# sensor.net
KiCad netlist of a schematic drawn in EAGLE
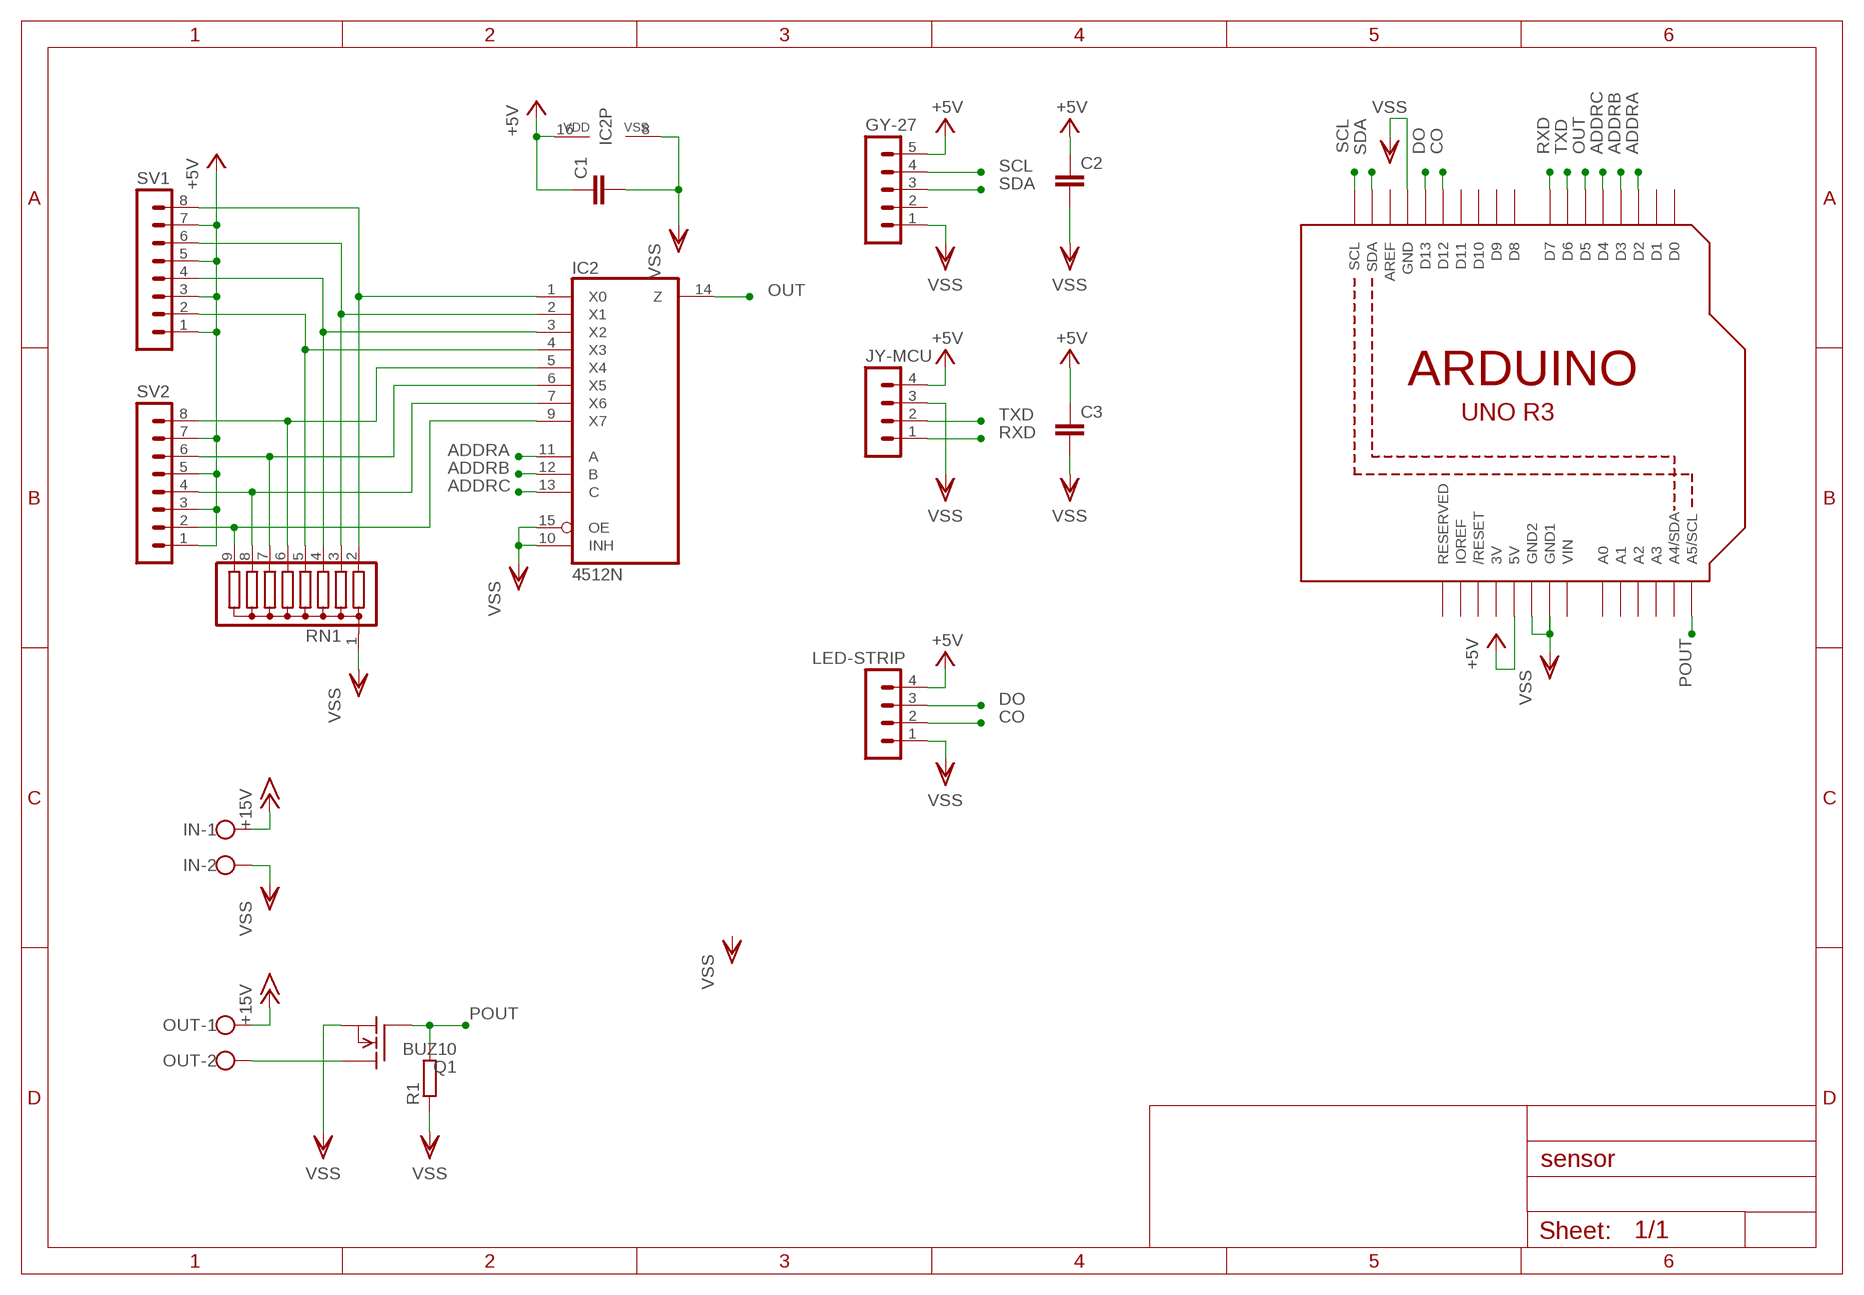
[diagram p0: schematic, sheet 1]

(export (version "E")
  (design (tool "Eeschema 10.0.6"))
  (components
    (comp (ref "C1")
      (value "C-EUC0805")
      (footprint "eagle-import:C0805")
      (libsource (lib "eagle-import") (part "C-EUC0805"))
    )
    (comp (ref "C2")
      (value "C-EUC0805")
      (footprint "eagle-import:C0805")
      (libsource (lib "eagle-import") (part "C-EUC0805"))
    )
    (comp (ref "C3")
      (value "C-EUC0805")
      (footprint "eagle-import:C0805")
      (libsource (lib "eagle-import") (part "C-EUC0805"))
    )
    (comp (ref "GY-27")
      (value "MA05-1")
      (footprint "eagle-import:MA05-1")
      (libsource (lib "eagle-import") (part "MA05-1"))
    )
    (comp (ref "IC2")
      (value "4512N")
      (footprint "eagle-import:DIL16")
      (libsource (lib "eagle-import") (part "4512N"))
    )
    (comp (ref "IN")
      (value "W237-102")
      (footprint "eagle-import:W237-102")
      (fields (field (name "MPN") "237-102"))
      (libsource (lib "eagle-import") (part "W237-102"))
    )
    (comp (ref "JY-MCU")
      (value "MA04-1")
      (footprint "eagle-import:MA04-1")
      (libsource (lib "eagle-import") (part "MA04-1"))
    )
    (comp (ref "LED-STRIP")
      (value "MA04-1")
      (footprint "eagle-import:MA04-1")
      (libsource (lib "eagle-import") (part "MA04-1"))
    )
    (comp (ref "OUT")
      (value "W237-102")
      (footprint "eagle-import:W237-102")
      (fields (field (name "MPN") "237-102"))
      (libsource (lib "eagle-import") (part "W237-102"))
    )
    (comp (ref "Q1")
      (value "BUZ10")
      (footprint "eagle-import:TO220")
      (libsource (lib "eagle-import") (part "BUZ10"))
    )
    (comp (ref "R1")
      (value "R-EU_M0805")
      (footprint "eagle-import:M0805")
      (libsource (lib "eagle-import") (part "R-EU_M0805"))
    )
    (comp (ref "RN1")
      (value "G08R")
      (footprint "eagle-import:SIL9")
      (libsource (lib "eagle-import") (part "G08R"))
    )
    (comp (ref "SV1")
      (value "MA08-1W")
      (footprint "eagle-import:MA08-1W")
      (libsource (lib "eagle-import") (part "MA08-1W"))
    )
    (comp (ref "SV2")
      (value "MA08-1W")
      (footprint "eagle-import:MA08-1W")
      (libsource (lib "eagle-import") (part "MA08-1W"))
    )
    (comp (ref "U1")
      (value "ARDUINOR3-DIMENSION")
      (footprint "eagle-import:ARDUINOR3")
      (libsource (lib "eagle-import") (part "ARDUINOR3-DIMENSION"))
    )
  )
  (nets
    (net (code "1") (name "+5V") (class "Default")
      (node (ref "C1") (pin "1") (pinfunction "1_1") (pintype "passive"))
      (node (ref "C2") (pin "1") (pinfunction "1_1") (pintype "passive"))
      (node (ref "C3") (pin "1") (pinfunction "1_1") (pintype "passive"))
      (node (ref "GY-27") (pin "5") (pinfunction "5_5") (pintype "passive"))
      (node (ref "IC2") (pin "16") (pinfunction "VDD_16") (pintype "power_in"))
      (node (ref "JY-MCU") (pin "4") (pinfunction "4_4") (pintype "passive"))
      (node (ref "LED-STRIP") (pin "4") (pinfunction "4_4") (pintype "passive"))
      (node (ref "SV1") (pin "1") (pinfunction "1_1") (pintype "passive"))
      (node (ref "SV1") (pin "3") (pinfunction "3_3") (pintype "passive"))
      (node (ref "SV1") (pin "5") (pinfunction "5_5") (pintype "passive"))
      (node (ref "SV1") (pin "7") (pinfunction "7_7") (pintype "passive"))
      (node (ref "SV2") (pin "1") (pinfunction "1_1") (pintype "passive"))
      (node (ref "SV2") (pin "3") (pinfunction "3_3") (pintype "passive"))
      (node (ref "SV2") (pin "5") (pinfunction "5_5") (pintype "passive"))
      (node (ref "SV2") (pin "7") (pinfunction "7_7") (pintype "passive"))
      (node (ref "U1") (pin "5V") (pinfunction "5V_5V") (pintype "power_in"))
    )
    (net (code "2") (name "+15V") (class "Default")
      (node (ref "IN") (pin "1") (pinfunction "KL_1") (pintype "passive"))
      (node (ref "OUT") (pin "1") (pinfunction "KL_1") (pintype "passive"))
    )
    (net (code "3") (name "/3V") (class "Default")
      (node (ref "U1") (pin "3V") (pinfunction "3V_3V") (pintype "power_in"))
    )
    (net (code "4") (name "/ADDRA") (class "Default")
      (node (ref "IC2") (pin "11") (pinfunction "A_11") (pintype "input"))
      (node (ref "U1") (pin "D2") (pinfunction "D2_D2") (pintype "bidirectional"))
    )
    (net (code "5") (name "/ADDRB") (class "Default")
      (node (ref "IC2") (pin "12") (pinfunction "B_12") (pintype "input"))
      (node (ref "U1") (pin "D3") (pinfunction "D3_D3") (pintype "bidirectional"))
    )
    (net (code "6") (name "/ADDRC") (class "Default")
      (node (ref "IC2") (pin "13") (pinfunction "C_13") (pintype "input"))
      (node (ref "U1") (pin "D4") (pinfunction "D4_D4") (pintype "bidirectional"))
    )
    (net (code "7") (name "/CO") (class "Default")
      (node (ref "LED-STRIP") (pin "2") (pinfunction "2_2") (pintype "passive"))
      (node (ref "U1") (pin "D12") (pinfunction "D12_D12") (pintype "bidirectional"))
    )
    (net (code "8") (name "/DO") (class "Default")
      (node (ref "LED-STRIP") (pin "3") (pinfunction "3_3") (pintype "passive"))
      (node (ref "U1") (pin "D13") (pinfunction "D13_D13") (pintype "bidirectional"))
    )
    (net (code "9") (name "/OUT") (class "Default")
      (node (ref "IC2") (pin "14") (pinfunction "Z_14") (pintype "tri_state"))
      (node (ref "U1") (pin "D5") (pinfunction "D5_D5") (pintype "bidirectional"))
    )
    (net (code "10") (name "/POUT") (class "Default")
      (node (ref "Q1") (pin "1") (pinfunction "G_1") (pintype "passive"))
      (node (ref "R1") (pin "2") (pinfunction "2_2") (pintype "passive"))
      (node (ref "U1") (pin "A5") (pinfunction "A5/SCL_A5") (pintype "bidirectional"))
    )
    (net (code "11") (name "/RXD") (class "Default")
      (node (ref "JY-MCU") (pin "1") (pinfunction "1_1") (pintype "passive"))
      (node (ref "U1") (pin "D7") (pinfunction "D7_D7") (pintype "bidirectional"))
    )
    (net (code "12") (name "/SCL") (class "Default")
      (node (ref "GY-27") (pin "4") (pinfunction "4_4") (pintype "passive"))
      (node (ref "U1") (pin "SCL") (pinfunction "SCL_SCL") (pintype "bidirectional"))
    )
    (net (code "13") (name "/SDA") (class "Default")
      (node (ref "GY-27") (pin "3") (pinfunction "3_3") (pintype "passive"))
      (node (ref "U1") (pin "SDA") (pinfunction "SDA_SDA") (pintype "bidirectional"))
    )
    (net (code "14") (name "/TXD") (class "Default")
      (node (ref "JY-MCU") (pin "2") (pinfunction "2_2") (pintype "passive"))
      (node (ref "U1") (pin "D6") (pinfunction "D6_D6") (pintype "bidirectional"))
    )
    (net (code "15") (name "/VIN") (class "Default")
      (node (ref "U1") (pin "VIN") (pinfunction "VIN_VIN") (pintype "power_in"))
    )
    (net (code "16") (name "Net-(IC2A-X0)") (class "Default")
      (node (ref "IC2") (pin "1") (pinfunction "X0_1") (pintype "input"))
      (node (ref "RN1") (pin "2") (pinfunction "2_2") (pintype "passive"))
      (node (ref "SV1") (pin "8") (pinfunction "8_8") (pintype "passive"))
    )
    (net (code "17") (name "Net-(IC2A-X1)") (class "Default")
      (node (ref "IC2") (pin "2") (pinfunction "X1_2") (pintype "input"))
      (node (ref "RN1") (pin "3") (pinfunction "3_3") (pintype "passive"))
      (node (ref "SV1") (pin "6") (pinfunction "6_6") (pintype "passive"))
    )
    (net (code "18") (name "Net-(IC2A-X2)") (class "Default")
      (node (ref "IC2") (pin "3") (pinfunction "X2_3") (pintype "input"))
      (node (ref "RN1") (pin "4") (pinfunction "4_4") (pintype "passive"))
      (node (ref "SV1") (pin "4") (pinfunction "4_4") (pintype "passive"))
    )
    (net (code "19") (name "Net-(IC2A-X3)") (class "Default")
      (node (ref "IC2") (pin "4") (pinfunction "X3_4") (pintype "input"))
      (node (ref "RN1") (pin "5") (pinfunction "5_5") (pintype "passive"))
      (node (ref "SV1") (pin "2") (pinfunction "2_2") (pintype "passive"))
    )
    (net (code "20") (name "Net-(IC2A-X4)") (class "Default")
      (node (ref "IC2") (pin "5") (pinfunction "X4_5") (pintype "input"))
      (node (ref "RN1") (pin "6") (pinfunction "6_6") (pintype "passive"))
      (node (ref "SV2") (pin "8") (pinfunction "8_8") (pintype "passive"))
    )
    (net (code "21") (name "Net-(IC2A-X5)") (class "Default")
      (node (ref "IC2") (pin "6") (pinfunction "X5_6") (pintype "input"))
      (node (ref "RN1") (pin "7") (pinfunction "7_7") (pintype "passive"))
      (node (ref "SV2") (pin "6") (pinfunction "6_6") (pintype "passive"))
    )
    (net (code "22") (name "Net-(IC2A-X6)") (class "Default")
      (node (ref "IC2") (pin "7") (pinfunction "X6_7") (pintype "input"))
      (node (ref "RN1") (pin "8") (pinfunction "8_8") (pintype "passive"))
      (node (ref "SV2") (pin "4") (pinfunction "4_4") (pintype "passive"))
    )
    (net (code "23") (name "Net-(IC2A-X7)") (class "Default")
      (node (ref "IC2") (pin "9") (pinfunction "X7_9") (pintype "input"))
      (node (ref "RN1") (pin "9") (pinfunction "9_9") (pintype "passive"))
      (node (ref "SV2") (pin "2") (pinfunction "2_2") (pintype "passive"))
    )
    (net (code "24") (name "Net-(OUTB-KL)") (class "Default")
      (node (ref "OUT") (pin "2") (pinfunction "KL_2") (pintype "passive"))
      (node (ref "Q1") (pin "2") (pinfunction "D_2") (pintype "passive"))
    )
    (net (code "25") (name "VSS") (class "Default")
      (node (ref "C1") (pin "2") (pinfunction "2_2") (pintype "passive"))
      (node (ref "C2") (pin "2") (pinfunction "2_2") (pintype "passive"))
      (node (ref "C3") (pin "2") (pinfunction "2_2") (pintype "passive"))
      (node (ref "GY-27") (pin "1") (pinfunction "1_1") (pintype "passive"))
      (node (ref "IC2") (pin "10") (pinfunction "INH_10") (pintype "input"))
      (node (ref "IC2") (pin "15") (pinfunction "OE_15") (pintype "input"))
      (node (ref "IC2") (pin "8") (pinfunction "VSS_8") (pintype "power_in"))
      (node (ref "IN") (pin "2") (pinfunction "KL_2") (pintype "passive"))
      (node (ref "JY-MCU") (pin "3") (pinfunction "3_3") (pintype "passive"))
      (node (ref "LED-STRIP") (pin "1") (pinfunction "1_1") (pintype "passive"))
      (node (ref "Q1") (pin "3") (pinfunction "S_3") (pintype "passive"))
      (node (ref "R1") (pin "1") (pinfunction "1_1") (pintype "passive"))
      (node (ref "RN1") (pin "1") (pinfunction "1_1") (pintype "passive"))
      (node (ref "U1") (pin "GND") (pinfunction "GND_GND") (pintype "power_in"))
      (node (ref "U1") (pin "GND1") (pinfunction "GND1_GND1") (pintype "power_in"))
      (node (ref "U1") (pin "GND2") (pinfunction "GND2_GND2") (pintype "power_in"))
    )
    (net (code "26") (name "unconnected-(GY-27-Pad2)") (class "Default")
      (node (ref "GY-27") (pin "2") (pinfunction "2_2") (pintype "passive"))
    )
    (net (code "27") (name "unconnected-(U1-A4{slash}SDA-PadA4)") (class "Default")
      (node (ref "U1") (pin "A4") (pinfunction "A4/SDA_A4") (pintype "bidirectional"))
    )
    (net (code "28") (name "unconnected-(U1-PadA0)") (class "Default")
      (node (ref "U1") (pin "A0") (pinfunction "A0_A0") (pintype "bidirectional"))
    )
    (net (code "29") (name "unconnected-(U1-PadA1)") (class "Default")
      (node (ref "U1") (pin "A1") (pinfunction "A1_A1") (pintype "bidirectional"))
    )
    (net (code "30") (name "unconnected-(U1-PadA2)") (class "Default")
      (node (ref "U1") (pin "A2") (pinfunction "A2_A2") (pintype "bidirectional"))
    )
    (net (code "31") (name "unconnected-(U1-PadA3)") (class "Default")
      (node (ref "U1") (pin "A3") (pinfunction "A3_A3") (pintype "bidirectional"))
    )
    (net (code "32") (name "unconnected-(U1-PadAREF)") (class "Default")
      (node (ref "U1") (pin "AREF") (pinfunction "AREF_AREF") (pintype "bidirectional"))
    )
    (net (code "33") (name "unconnected-(U1-PadD0)") (class "Default")
      (node (ref "U1") (pin "D0") (pinfunction "D0_D0") (pintype "bidirectional"))
    )
    (net (code "34") (name "unconnected-(U1-PadD1)") (class "Default")
      (node (ref "U1") (pin "D1") (pinfunction "D1_D1") (pintype "bidirectional"))
    )
    (net (code "35") (name "unconnected-(U1-PadD8)") (class "Default")
      (node (ref "U1") (pin "D8") (pinfunction "D8_D8") (pintype "bidirectional"))
    )
    (net (code "36") (name "unconnected-(U1-PadD9)") (class "Default")
      (node (ref "U1") (pin "D9") (pinfunction "D9_D9") (pintype "bidirectional"))
    )
    (net (code "37") (name "unconnected-(U1-PadD10)") (class "Default")
      (node (ref "U1") (pin "D10") (pinfunction "D10_D10") (pintype "bidirectional"))
    )
    (net (code "38") (name "unconnected-(U1-PadD11)") (class "Default")
      (node (ref "U1") (pin "D11") (pinfunction "D11_D11") (pintype "bidirectional"))
    )
    (net (code "39") (name "unconnected-(U1-PadIOREF)") (class "Default")
      (node (ref "U1") (pin "IOREF") (pinfunction "IOREF_IOREF") (pintype "output"))
    )
    (net (code "40") (name "unconnected-(U1-PadRESERVED)") (class "Default")
      (node (ref "U1") (pin "RESERVED") (pinfunction "RESERVED_RESERVED") (pintype "no_connect"))
    )
    (net (code "41") (name "unconnected-(U1-{slash}RESET-PadRESET)") (class "Default")
      (node (ref "U1") (pin "RESET") (pinfunction "/RESET_RESET") (pintype "bidirectional"))
    )
  )
)
